# V1.net
KiCad netlist of a schematic drawn in EAGLE
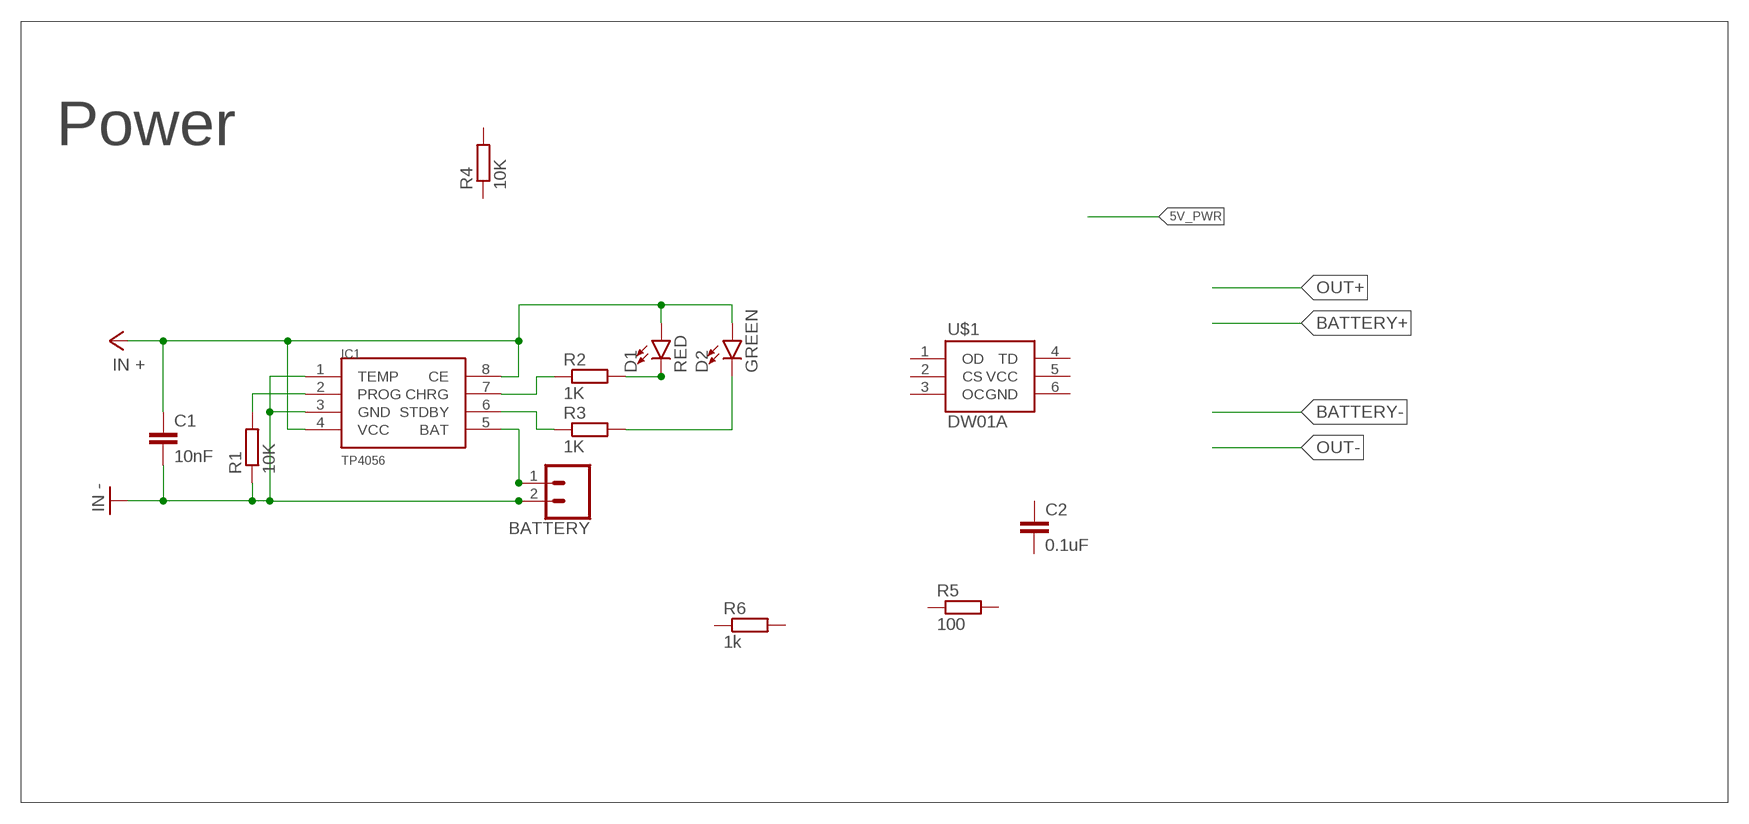
[diagram p0: schematic, sheet 1]

(export (version "E")
  (design (tool "Eeschema 10.0.6"))
  (components
    (comp (ref "BATTERY")
      (value "CONN_02")
      (footprint "eagle-import:1X02")
      (libsource (lib "eagle-import") (part "CONN_02"))
    )
    (comp (ref "C1")
      (value "10nF")
      (footprint "eagle-import:0603")
      (libsource (lib "eagle-import") (part "10NF-0603-50V-10%"))
    )
    (comp (ref "C2")
      (value "0.1uF")
      (footprint "eagle-import:0603")
      (libsource (lib "eagle-import") (part "10NF-0603-50V-10%"))
    )
    (comp (ref "D1")
      (value "RED")
      (footprint "eagle-import:LED-0603")
      (libsource (lib "eagle-import") (part "LED-RED0603"))
    )
    (comp (ref "D2")
      (value "GREEN")
      (footprint "eagle-import:LED-0603")
      (libsource (lib "eagle-import") (part "LED-RED0603"))
    )
    (comp (ref "IC1")
      (value "TP4056")
      (footprint "eagle-import:SOP-8")
      (libsource (lib "eagle-import") (part "TP4056"))
    )
    (comp (ref "R1")
      (value "10K")
      (footprint "eagle-import:R0603")
      (libsource (lib "eagle-import") (part "R-EU_R0603"))
    )
    (comp (ref "R2")
      (value "1K")
      (footprint "eagle-import:R0603")
      (libsource (lib "eagle-import") (part "R-EU_R0603"))
    )
    (comp (ref "R3")
      (value "1K")
      (footprint "eagle-import:R0603")
      (libsource (lib "eagle-import") (part "R-EU_R0603"))
    )
    (comp (ref "R4")
      (value "10K")
      (footprint "eagle-import:R0603")
      (libsource (lib "eagle-import") (part "R-EU_R0603"))
    )
    (comp (ref "R5")
      (value "100")
      (footprint "eagle-import:R0603")
      (libsource (lib "eagle-import") (part "R-EU_R0603"))
    )
    (comp (ref "R6")
      (value "1k")
      (footprint "eagle-import:R0603")
      (libsource (lib "eagle-import") (part "R-EU_R0603"))
    )
    (comp (ref "U$1")
      (value "DW01A")
      (footprint "eagle-import:DW01A_V2")
      (libsource (lib "eagle-import") (part "DW01A"))
    )
  )
  (nets
    (net (code "4") (name "IN +") (class "Default")
      (node (ref "C1") (pin "1") (pinfunction "1_1") (pintype "passive"))
      (node (ref "D1") (pin "A") (pinfunction "A_A") (pintype "passive"))
      (node (ref "D2") (pin "A") (pinfunction "A_A") (pintype "passive"))
      (node (ref "IC1") (pin "4") (pinfunction "VCC_4") (pintype "bidirectional"))
      (node (ref "IC1") (pin "8") (pinfunction "CE_8") (pintype "bidirectional"))
    )
    (net (code "5") (name "IN -") (class "Default")
      (node (ref "BATTERY") (pin "2") (pinfunction "2_2") (pintype "passive"))
      (node (ref "C1") (pin "2") (pinfunction "2_2") (pintype "passive"))
      (node (ref "IC1") (pin "1") (pinfunction "TEMP_1") (pintype "bidirectional"))
      (node (ref "IC1") (pin "3") (pinfunction "GND_3") (pintype "bidirectional"))
      (node (ref "R1") (pin "1") (pinfunction "1_1") (pintype "passive"))
    )
    (net (code "6") (name "Net-(D1-PadC)") (class "Default")
      (node (ref "D1") (pin "C") (pinfunction "C_C") (pintype "passive"))
      (node (ref "R2") (pin "2") (pinfunction "2_2") (pintype "passive"))
    )
    (net (code "7") (name "Net-(D2-PadC)") (class "Default")
      (node (ref "D2") (pin "C") (pinfunction "C_C") (pintype "passive"))
      (node (ref "R3") (pin "2") (pinfunction "2_2") (pintype "passive"))
    )
    (net (code "8") (name "Net-(IC1-BAT)") (class "Default")
      (node (ref "BATTERY") (pin "1") (pinfunction "1_1") (pintype "passive"))
      (node (ref "IC1") (pin "5") (pinfunction "BAT_5") (pintype "bidirectional"))
    )
    (net (code "9") (name "Net-(IC1-CHRG)") (class "Default")
      (node (ref "IC1") (pin "7") (pinfunction "CHRG_7") (pintype "bidirectional"))
      (node (ref "R2") (pin "1") (pinfunction "1_1") (pintype "passive"))
    )
    (net (code "10") (name "Net-(IC1-PROG)") (class "Default")
      (node (ref "IC1") (pin "2") (pinfunction "PROG_2") (pintype "bidirectional"))
      (node (ref "R1") (pin "2") (pinfunction "2_2") (pintype "passive"))
    )
    (net (code "11") (name "Net-(IC1-STDBY)") (class "Default")
      (node (ref "IC1") (pin "6") (pinfunction "STDBY_6") (pintype "bidirectional"))
      (node (ref "R3") (pin "1") (pinfunction "1_1") (pintype "passive"))
    )
    (net (code "14") (name "unconnected-(C2-Pad1)") (class "Default")
      (node (ref "C2") (pin "1") (pinfunction "1_1") (pintype "passive"))
    )
    (net (code "15") (name "unconnected-(C2-Pad2)") (class "Default")
      (node (ref "C2") (pin "2") (pinfunction "2_2") (pintype "passive"))
    )
    (net (code "16") (name "unconnected-(R4-Pad1)") (class "Default")
      (node (ref "R4") (pin "1") (pinfunction "1_1") (pintype "passive"))
    )
    (net (code "17") (name "unconnected-(R4-Pad2)") (class "Default")
      (node (ref "R4") (pin "2") (pinfunction "2_2") (pintype "passive"))
    )
    (net (code "18") (name "unconnected-(R5-Pad1)") (class "Default")
      (node (ref "R5") (pin "1") (pinfunction "1_1") (pintype "passive"))
    )
    (net (code "19") (name "unconnected-(R5-Pad2)") (class "Default")
      (node (ref "R5") (pin "2") (pinfunction "2_2") (pintype "passive"))
    )
    (net (code "20") (name "unconnected-(R6-Pad1)") (class "Default")
      (node (ref "R6") (pin "1") (pinfunction "1_1") (pintype "passive"))
    )
    (net (code "21") (name "unconnected-(R6-Pad2)") (class "Default")
      (node (ref "R6") (pin "2") (pinfunction "2_2") (pintype "passive"))
    )
    (net (code "22") (name "unconnected-(U$1-CS-Pad2)") (class "Default")
      (node (ref "U$1") (pin "2") (pinfunction "CS_2") (pintype "bidirectional"))
    )
    (net (code "23") (name "unconnected-(U$1-GND-Pad6)") (class "Default")
      (node (ref "U$1") (pin "6") (pinfunction "GND_6") (pintype "bidirectional"))
    )
    (net (code "24") (name "unconnected-(U$1-OC-Pad3)") (class "Default")
      (node (ref "U$1") (pin "3") (pinfunction "OC_3") (pintype "bidirectional"))
    )
    (net (code "25") (name "unconnected-(U$1-OD-Pad1)") (class "Default")
      (node (ref "U$1") (pin "1") (pinfunction "OD_1") (pintype "bidirectional"))
    )
    (net (code "26") (name "unconnected-(U$1-TD-Pad4)") (class "Default")
      (node (ref "U$1") (pin "4") (pinfunction "TD_4") (pintype "bidirectional"))
    )
    (net (code "27") (name "unconnected-(U$1-VCC-Pad5)") (class "Default")
      (node (ref "U$1") (pin "5") (pinfunction "VCC_5") (pintype "bidirectional"))
    )
  )
)
